# tdr.net
KiCad netlist of a schematic drawn in EAGLE
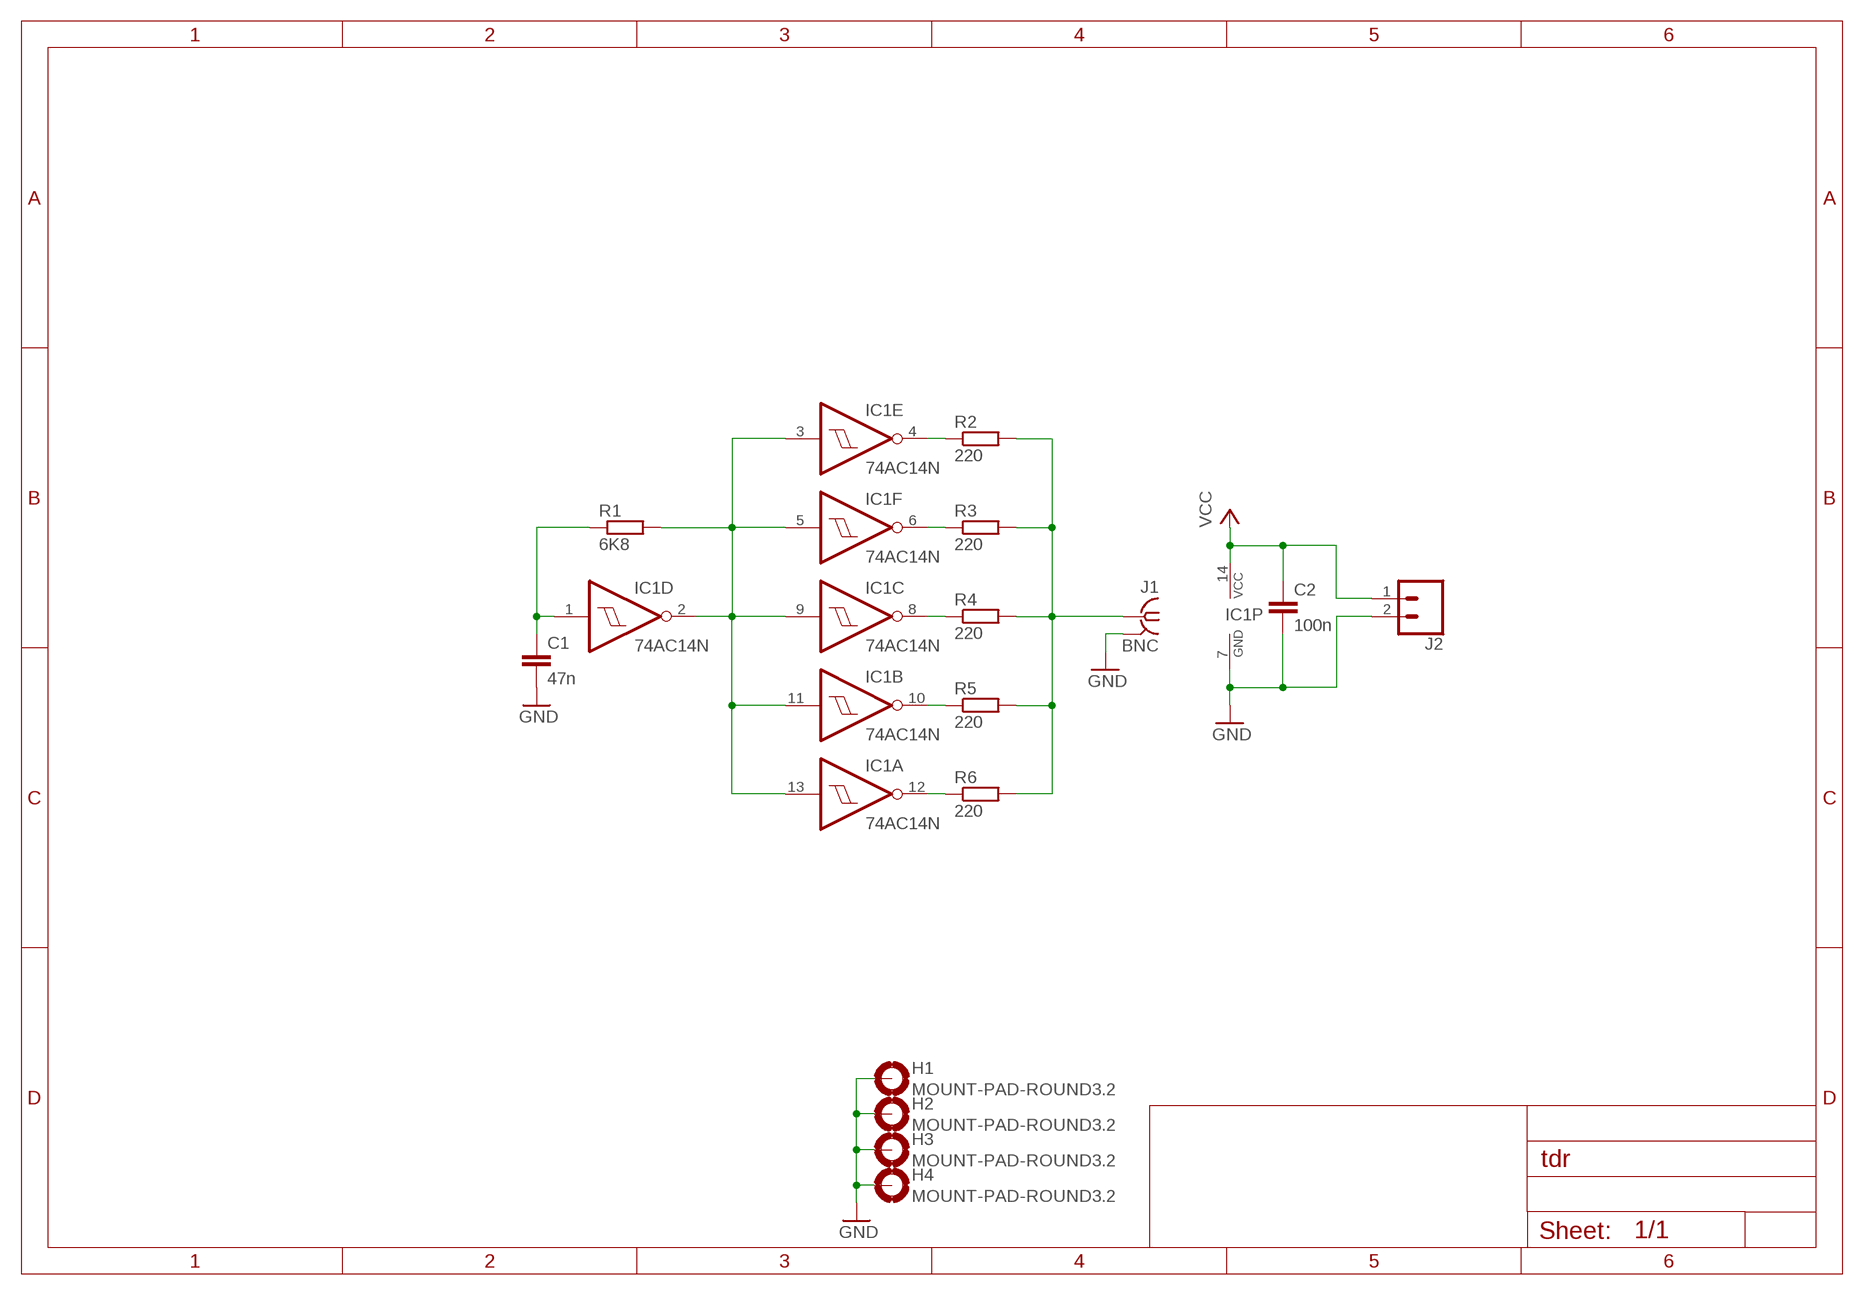
[diagram p0: schematic, sheet 1]

(export (version "E")
  (design (tool "Eeschema 10.0.6"))
  (components
    (comp (ref "C1")
      (value "47n")
      (footprint "eagle-import:C075-032X103")
      (libsource (lib "eagle-import") (part "C-EU075-032X103"))
    )
    (comp (ref "C2")
      (value "100n")
      (footprint "eagle-import:C075-032X103")
      (libsource (lib "eagle-import") (part "C-EU075-032X103"))
    )
    (comp (ref "H1")
      (value "MOUNT-PAD-ROUND3.2")
      (footprint "eagle-import:3,2-PAD")
      (libsource (lib "eagle-import") (part "MOUNT-PAD-ROUND3.2"))
    )
    (comp (ref "H2")
      (value "MOUNT-PAD-ROUND3.2")
      (footprint "eagle-import:3,2-PAD")
      (libsource (lib "eagle-import") (part "MOUNT-PAD-ROUND3.2"))
    )
    (comp (ref "H3")
      (value "MOUNT-PAD-ROUND3.2")
      (footprint "eagle-import:3,2-PAD")
      (libsource (lib "eagle-import") (part "MOUNT-PAD-ROUND3.2"))
    )
    (comp (ref "H4")
      (value "MOUNT-PAD-ROUND3.2")
      (footprint "eagle-import:3,2-PAD")
      (libsource (lib "eagle-import") (part "MOUNT-PAD-ROUND3.2"))
    )
    (comp (ref "IC1")
      (value "74AC14N")
      (footprint "eagle-import:DIL14")
      (libsource (lib "eagle-import") (part "7414NAC"))
    )
    (comp (ref "J1")
      (value "BNC")
      (footprint "eagle-import:BNC_TYCO")
      (libsource (lib "eagle-import") (part "BNC"))
    )
    (comp (ref "J2")
      (value "CONN_023.5MM")
      (footprint "eagle-import:SCREWTERMINAL-3.5MM-2")
      (libsource (lib "eagle-import") (part "CONN_023.5MM"))
    )
    (comp (ref "R1")
      (value "6K8")
      (footprint "eagle-import:0207_10")
      (libsource (lib "eagle-import") (part "R-EU_0207/10"))
    )
    (comp (ref "R2")
      (value "220")
      (footprint "eagle-import:0207_10")
      (libsource (lib "eagle-import") (part "R-EU_0207/10"))
    )
    (comp (ref "R3")
      (value "220")
      (footprint "eagle-import:0207_10")
      (libsource (lib "eagle-import") (part "R-EU_0207/10"))
    )
    (comp (ref "R4")
      (value "220")
      (footprint "eagle-import:0207_10")
      (libsource (lib "eagle-import") (part "R-EU_0207/10"))
    )
    (comp (ref "R5")
      (value "220")
      (footprint "eagle-import:0207_10")
      (libsource (lib "eagle-import") (part "R-EU_0207/10"))
    )
    (comp (ref "R6")
      (value "220")
      (footprint "eagle-import:0207_10")
      (libsource (lib "eagle-import") (part "R-EU_0207/10"))
    )
  )
  (nets
    (net (code "1") (name "GND") (class "Default")
      (node (ref "C1") (pin "2") (pinfunction "2_2") (pintype "passive"))
      (node (ref "C2") (pin "2") (pinfunction "2_2") (pintype "passive"))
      (node (ref "H1") (pin "B3,2") (pinfunction "MOUNT_B3,2") (pintype "passive"))
      (node (ref "H2") (pin "B3,2") (pinfunction "MOUNT_B3,2") (pintype "passive"))
      (node (ref "H3") (pin "B3,2") (pinfunction "MOUNT_B3,2") (pintype "passive"))
      (node (ref "H4") (pin "B3,2") (pinfunction "MOUNT_B3,2") (pintype "passive"))
      (node (ref "IC1") (pin "7") (pinfunction "GND_7") (pintype "power_in"))
      (node (ref "J1") (pin "G") (pinfunction "GND_G") (pintype "power_in"))
      (node (ref "J2") (pin "2") (pinfunction "2_2") (pintype "passive"))
    )
    (net (code "2") (name "Net-(IC1A-I)") (class "Default")
      (node (ref "IC1") (pin "11") (pinfunction "I_11") (pintype "input"))
      (node (ref "IC1") (pin "13") (pinfunction "I_13") (pintype "input"))
      (node (ref "IC1") (pin "2") (pinfunction "O_2") (pintype "output"))
      (node (ref "IC1") (pin "3") (pinfunction "I_3") (pintype "input"))
      (node (ref "IC1") (pin "5") (pinfunction "I_5") (pintype "input"))
      (node (ref "IC1") (pin "9") (pinfunction "I_9") (pintype "input"))
      (node (ref "R1") (pin "2") (pinfunction "2_2") (pintype "passive"))
    )
    (net (code "3") (name "Net-(IC1A-O)") (class "Default")
      (node (ref "IC1") (pin "12") (pinfunction "O_12") (pintype "output"))
      (node (ref "R6") (pin "1") (pinfunction "1_1") (pintype "passive"))
    )
    (net (code "4") (name "Net-(IC1B-O)") (class "Default")
      (node (ref "IC1") (pin "10") (pinfunction "O_10") (pintype "output"))
      (node (ref "R5") (pin "1") (pinfunction "1_1") (pintype "passive"))
    )
    (net (code "5") (name "Net-(IC1C-O)") (class "Default")
      (node (ref "IC1") (pin "8") (pinfunction "O_8") (pintype "output"))
      (node (ref "R4") (pin "1") (pinfunction "1_1") (pintype "passive"))
    )
    (net (code "6") (name "Net-(IC1D-I)") (class "Default")
      (node (ref "C1") (pin "1") (pinfunction "1_1") (pintype "passive"))
      (node (ref "IC1") (pin "1") (pinfunction "I_1") (pintype "input"))
      (node (ref "R1") (pin "1") (pinfunction "1_1") (pintype "passive"))
    )
    (net (code "7") (name "Net-(IC1E-O)") (class "Default")
      (node (ref "IC1") (pin "4") (pinfunction "O_4") (pintype "output"))
      (node (ref "R2") (pin "1") (pinfunction "1_1") (pintype "passive"))
    )
    (net (code "8") (name "Net-(IC1F-O)") (class "Default")
      (node (ref "IC1") (pin "6") (pinfunction "O_6") (pintype "output"))
      (node (ref "R3") (pin "1") (pinfunction "1_1") (pintype "passive"))
    )
    (net (code "9") (name "Net-(J1-1)") (class "Default")
      (node (ref "J1") (pin "C") (pinfunction "1_C") (pintype "passive"))
      (node (ref "R2") (pin "2") (pinfunction "2_2") (pintype "passive"))
      (node (ref "R3") (pin "2") (pinfunction "2_2") (pintype "passive"))
      (node (ref "R4") (pin "2") (pinfunction "2_2") (pintype "passive"))
      (node (ref "R5") (pin "2") (pinfunction "2_2") (pintype "passive"))
      (node (ref "R6") (pin "2") (pinfunction "2_2") (pintype "passive"))
    )
    (net (code "10") (name "VCC") (class "Default")
      (node (ref "C2") (pin "1") (pinfunction "1_1") (pintype "passive"))
      (node (ref "IC1") (pin "14") (pinfunction "VCC_14") (pintype "power_in"))
      (node (ref "J2") (pin "1") (pinfunction "1_1") (pintype "passive"))
    )
  )
)
